# warship_demo_4.net
KiCad netlist of a schematic drawn in Altium Designer
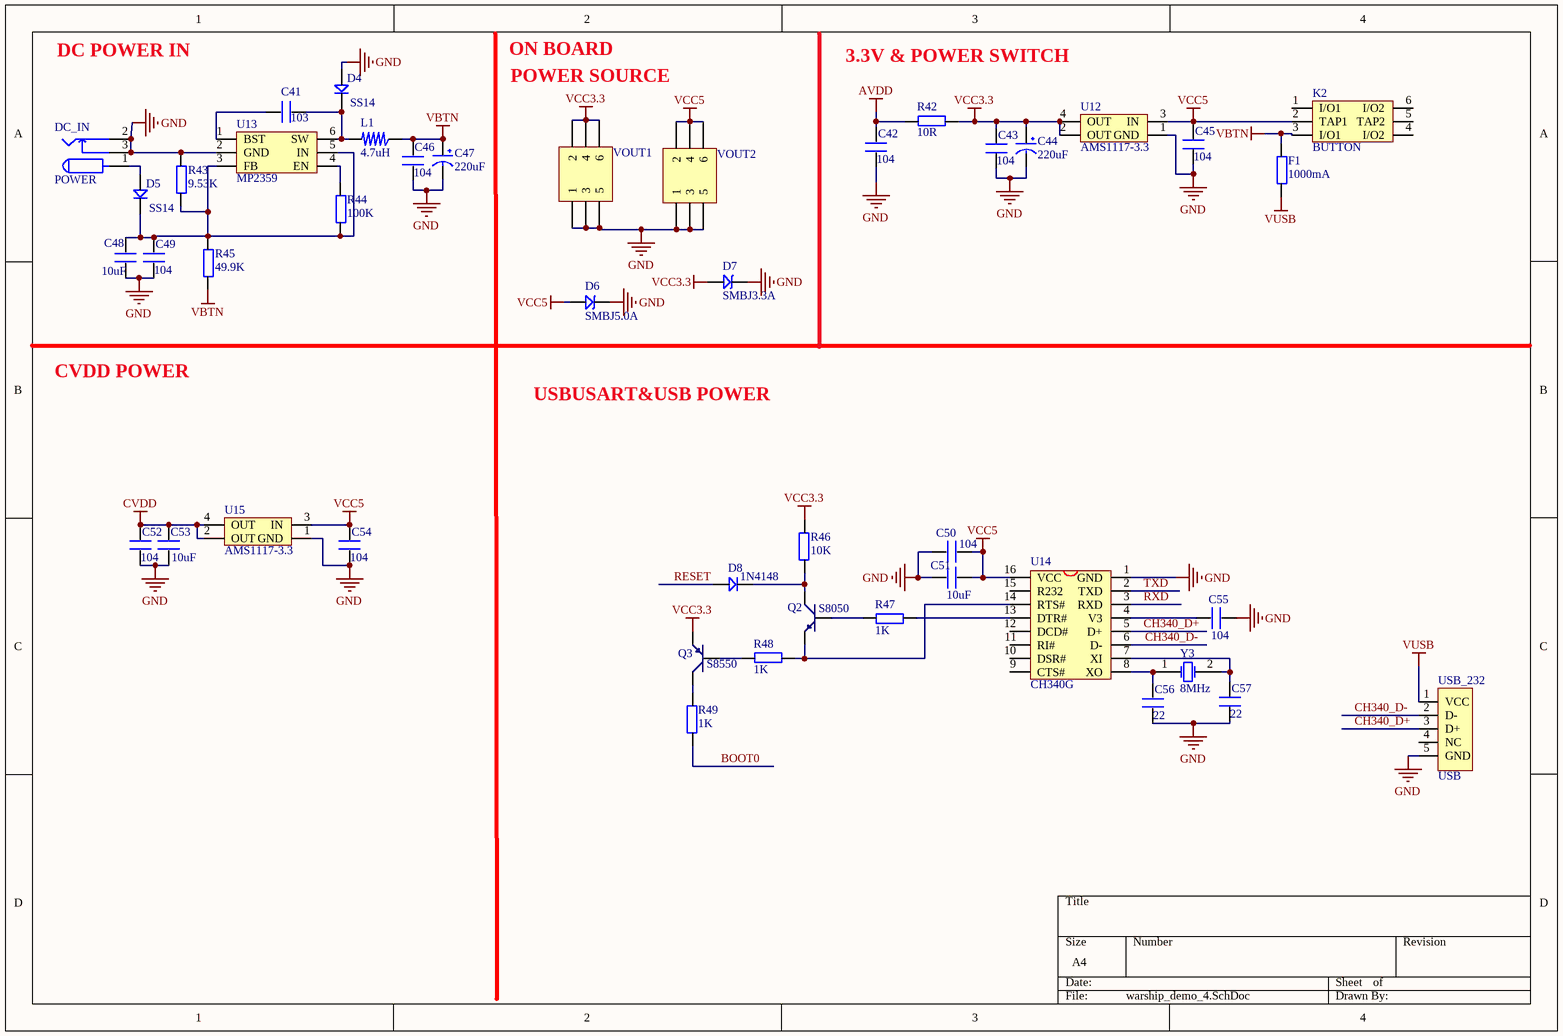
[diagram p0: warship_demo_4.SchDoc]

(export (version "E")
  (design (tool "Eeschema 10.0.6"))
  (components
    (comp (ref "C41") (value "103") (footprint "0603P") (libsource (lib "WarShip V3 STM32103封装库") (part "C")))
    (comp (ref "C42") (value "104") (footprint "0603P") (libsource (lib "WarShip V3 STM32103封装库") (part "C")))
    (comp (ref "C43") (value "104") (footprint "0603P") (libsource (lib "WarShip V3 STM32103封装库") (part "C")))
    (comp (ref "C44")
      (value "220uF")
      (footprint "CC6.56.5")
      (libsource (lib "WarShip V3 STM32103封装库") (part "CAP"))
    )
    (comp (ref "C45") (value "104") (footprint "0603P") (libsource (lib "WarShip V3 STM32103封装库") (part "C")))
    (comp (ref "C46") (value "104") (footprint "0603P") (libsource (lib "WarShip V3 STM32103封装库") (part "C")))
    (comp (ref "C47")
      (value "220uF")
      (footprint "CC6.56.5")
      (libsource (lib "WarShip V3 STM32103封装库") (part "CAP"))
    )
    (comp (ref "C48") (value "10uF") (footprint "1206") (libsource (lib "WarShip V3 STM32103封装库") (part "C")))
    (comp (ref "C49") (value "104") (footprint "0603P") (libsource (lib "WarShip V3 STM32103封装库") (part "C")))
    (comp (ref "C50") (value "104") (footprint "0603P") (libsource (lib "WarShip V3 STM32103封装库") (part "C")))
    (comp (ref "C51") (value "10uF") (footprint "0805") (libsource (lib "WarShip V3 STM32103封装库") (part "C")))
    (comp (ref "C52") (value "104") (footprint "0603P") (libsource (lib "WarShip V3 STM32103封装库") (part "C")))
    (comp (ref "C53") (value "10uF") (footprint "0805") (libsource (lib "WarShip V3 STM32103封装库") (part "C")))
    (comp (ref "C54") (value "104") (footprint "0603P") (libsource (lib "WarShip V3 STM32103封装库") (part "C")))
    (comp (ref "C55") (value "104") (footprint "0603P") (libsource (lib "WarShip V3 STM32103封装库") (part "C")))
    (comp (ref "C56") (value "22") (footprint "0603P") (libsource (lib "WarShip V3 STM32103封装库") (part "C")))
    (comp (ref "C57") (value "22") (footprint "0603P") (libsource (lib "WarShip V3 STM32103封装库") (part "C")))
    (comp (ref "D4")
      (value "SS14")
      (footprint "DIODE_3*5.3")
      (libsource (lib "WarShip V3 STM32103封装库") (part "D"))
    )
    (comp (ref "D5")
      (value "SS14")
      (footprint "DIODE_3*5.3")
      (libsource (lib "WarShip V3 STM32103封装库") (part "D"))
    )
    (comp (ref "D6")
      (value "SMBJ5.0A")
      (footprint "SMBJ")
      (description "TVS")
      (libsource (lib "WarShip V3 STM32103封装库") (part "SMBJ"))
    )
    (comp (ref "D7")
      (value "SMBJ3.3A")
      (footprint "SMBJ")
      (description "TVS")
      (libsource (lib "WarShip V3 STM32103封装库") (part "SMBJ"))
    )
    (comp (ref "D8")
      (value "1N4148")
      (footprint "DIODE_SOP")
      (libsource (lib "WarShip V3 STM32103封装库") (part "D"))
    )
    (comp (ref "DC_IN")
      (value "POWER")
      (footprint "DC10B")
      (libsource (lib "WarShip V3 STM32103封装库") (part "POW"))
    )
    (comp (ref "F1")
      (value "1000mA")
      (footprint "0805")
      (libsource (lib "WarShip V3 STM32103封装库") (part "R"))
    )
    (comp (ref "K2")
      (value "BUTTON")
      (footprint "BTN8.5*8.5")
      (libsource (lib "WarShip V3 STM32103封装库") (part "BUTTON"))
    )
    (comp (ref "L1")
      (value "4.7uH")
      (footprint "L_SOP74")
      (libsource (lib "WarShip V3 STM32103封装库") (part "L_SOP"))
    )
    (comp (ref "Q2")
      (value "S8050")
      (footprint "SOT-23R")
      (description "8050/BCW846/BCW847")
      (libsource (lib "WarShip V3 STM32103封装库") (part "NPN"))
    )
    (comp (ref "Q3")
      (value "S8550")
      (footprint "SOT-23R")
      (description "8550/BCW68")
      (libsource (lib "WarShip V3 STM32103封装库") (part "PNP"))
    )
    (comp (ref "R42") (value "10R") (footprint "0603P") (libsource (lib "WarShip V3 STM32103封装库") (part "R")))
    (comp (ref "R43")
      (value "9.53K")
      (footprint "0603P")
      (libsource (lib "WarShip V3 STM32103封装库") (part "R"))
    )
    (comp (ref "R44")
      (value "100K")
      (footprint "0603P")
      (libsource (lib "WarShip V3 STM32103封装库") (part "R"))
    )
    (comp (ref "R45")
      (value "49.9K")
      (footprint "0603P")
      (libsource (lib "WarShip V3 STM32103封装库") (part "R"))
    )
    (comp (ref "R46") (value "10K") (footprint "0603P") (libsource (lib "WarShip V3 STM32103封装库") (part "R")))
    (comp (ref "R47") (value "1K") (footprint "0603P") (libsource (lib "WarShip V3 STM32103封装库") (part "R")))
    (comp (ref "R48") (value "1K") (footprint "0603P") (libsource (lib "WarShip V3 STM32103封装库") (part "R")))
    (comp (ref "R49") (value "1K") (footprint "0603P") (libsource (lib "WarShip V3 STM32103封装库") (part "R")))
    (comp (ref "U12")
      (value "AMS1117-3.3")
      (footprint "AMS1117")
      (libsource (lib "WarShip V3 STM32103封装库") (part "AMS1117"))
    )
    (comp (ref "U13")
      (value "MP2359")
      (footprint "SOT-23-6")
      (description "DC DC Step Down IC")
      (libsource (lib "WarShip V3 STM32103封装库") (part "MP2359"))
    )
    (comp (ref "U14")
      (value "CH340G")
      (footprint "SOP16M")
      (description "USB2UART")
      (libsource (lib "WarShip V3 STM32103封装库") (part "CH340G"))
    )
    (comp (ref "U15")
      (value "AMS1117-3.3")
      (footprint "AMS1117")
      (libsource (lib "WarShip V3 STM32103封装库") (part "AMS1117"))
    )
    (comp (ref "USB_232")
      (value "USB")
      (footprint "USB/SM0.8-6H5")
      (libsource (lib "WarShip V3 STM32103封装库") (part "USB5"))
    )
    (comp (ref "VOUT1")
      (value "Header 3X2")
      (footprint "HDR2X3")
      (description "Header, 3-Pin, Dual row")
      (fields (field (name "PUBLISHER") "Altium Limited"))
      (libsource (lib "WarShip V3 STM32103封装库") (part "Header 3X2"))
    )
    (comp (ref "VOUT2")
      (value "Header 3X2")
      (footprint "HDR2X3")
      (description "Header, 3-Pin, Dual row")
      (fields (field (name "PUBLISHER") "Altium Limited"))
      (libsource (lib "WarShip V3 STM32103封装库") (part "Header 3X2"))
    )
    (comp (ref "Y3")
      (value "8MHz")
      (footprint "XTAL_US")
      (description "Crystal Oscillator")
      (fields (field (name "PUBLISHER") "Altium Limited"))
      (libsource (lib "WarShip V3 STM32103封装库") (part "XTAL"))
    )
  )
  (nets
    (net (code "1") (name "/BOOT0") (class "Default") (node (ref "R49") (pin "2") (pintype "passive")))
    (net (code "2") (name "/CH340_D+") (class "Default")
      (node (ref "U14") (pin "5") (pinfunction "D+_5") (pintype "passive"))
      (node (ref "USB_232") (pin "3") (pinfunction "D+_3") (pintype "passive"))
    )
    (net (code "3") (name "/CH340_D-") (class "Default")
      (node (ref "U14") (pin "6") (pinfunction "D-_6") (pintype "passive"))
      (node (ref "USB_232") (pin "2") (pinfunction "D-_2") (pintype "passive"))
    )
    (net (code "4") (name "/RESET") (class "Default") (node (ref "D8") (pin "1") (pintype "passive")))
    (net (code "5") (name "/RXD") (class "Default")
      (node (ref "U14") (pin "3") (pinfunction "RXD_3") (pintype "passive"))
    )
    (net (code "6") (name "/TXD") (class "Default")
      (node (ref "U14") (pin "2") (pinfunction "TXD_2") (pintype "passive"))
    )
    (net (code "7") (name "AVDD") (class "Default")
      (node (ref "C42") (pin "2") (pintype "passive"))
      (node (ref "R42") (pin "2") (pintype "passive"))
    )
    (net (code "8") (name "CVDD") (class "Default")
      (node (ref "C52") (pin "2") (pintype "passive"))
      (node (ref "C53") (pin "2") (pintype "passive"))
      (node (ref "U15") (pin "2") (pinfunction "OUT_2") (pintype "passive"))
      (node (ref "U15") (pin "4") (pinfunction "OUT_4") (pintype "passive"))
    )
    (net (code "9") (name "GND") (class "Default")
      (node (ref "C42") (pin "1") (pintype "passive"))
      (node (ref "C43") (pin "1") (pintype "passive"))
      (node (ref "C44") (pin "2") (pinfunction "GND_2") (pintype "passive"))
      (node (ref "C45") (pin "1") (pintype "passive"))
      (node (ref "C46") (pin "1") (pintype "passive"))
      (node (ref "C47") (pin "2") (pinfunction "GND_2") (pintype "passive"))
      (node (ref "C48") (pin "1") (pintype "passive"))
      (node (ref "C49") (pin "1") (pintype "passive"))
      (node (ref "C50") (pin "2") (pintype "passive"))
      (node (ref "C51") (pin "1") (pintype "passive"))
      (node (ref "C52") (pin "1") (pintype "passive"))
      (node (ref "C53") (pin "1") (pintype "passive"))
      (node (ref "C54") (pin "1") (pintype "passive"))
      (node (ref "C55") (pin "1") (pintype "passive"))
      (node (ref "C56") (pin "1") (pintype "passive"))
      (node (ref "C57") (pin "1") (pintype "passive"))
      (node (ref "D4") (pin "1") (pintype "passive"))
      (node (ref "D6") (pin "2") (pintype "passive"))
      (node (ref "D7") (pin "2") (pintype "passive"))
      (node (ref "DC_IN") (pin "2") (pintype "passive"))
      (node (ref "DC_IN") (pin "3") (pintype "passive"))
      (node (ref "R43") (pin "2") (pintype "passive"))
      (node (ref "U12") (pin "1") (pinfunction "GND_1") (pintype "passive"))
      (node (ref "U13") (pin "2") (pinfunction "GND_2") (pintype "passive"))
      (node (ref "U14") (pin "1") (pinfunction "GND_1") (pintype "passive"))
      (node (ref "U15") (pin "1") (pinfunction "GND_1") (pintype "passive"))
      (node (ref "USB_232") (pin "5") (pinfunction "GND_5") (pintype "passive"))
      (node (ref "VOUT1") (pin "1") (pinfunction "1_1") (pintype "passive"))
      (node (ref "VOUT1") (pin "3") (pinfunction "3_3") (pintype "passive"))
      (node (ref "VOUT1") (pin "5") (pinfunction "5_5") (pintype "passive"))
      (node (ref "VOUT2") (pin "1") (pinfunction "1_1") (pintype "passive"))
      (node (ref "VOUT2") (pin "3") (pinfunction "3_3") (pintype "passive"))
      (node (ref "VOUT2") (pin "5") (pinfunction "5_5") (pintype "passive"))
    )
    (net (code "10") (name "Net-(D5-Pad1)") (class "Default")
      (node (ref "D5") (pin "1") (pintype "passive"))
      (node (ref "DC_IN") (pin "1") (pintype "passive"))
    )
    (net (code "11") (name "Net-(Q2-B)") (class "Default")
      (node (ref "Q2") (pin "2") (pinfunction "B_2") (pintype "passive"))
      (node (ref "R47") (pin "1") (pintype "passive"))
    )
    (net (code "12") (name "Net-(Q2-C)") (class "Default")
      (node (ref "D8") (pin "2") (pintype "passive"))
      (node (ref "Q2") (pin "3") (pinfunction "C_3") (pintype "passive"))
      (node (ref "R46") (pin "2") (pintype "passive"))
    )
    (net (code "13") (name "Net-(Q2-E)") (class "Default")
      (node (ref "Q2") (pin "1") (pinfunction "E_1") (pintype "passive"))
      (node (ref "R48") (pin "1") (pintype "passive"))
      (node (ref "U14") (pin "14") (pinfunction "RTS#_14") (pintype "passive"))
    )
    (net (code "14") (name "Net-(Q3-B)") (class "Default")
      (node (ref "Q3") (pin "2") (pinfunction "B_2") (pintype "passive"))
      (node (ref "R48") (pin "2") (pintype "passive"))
    )
    (net (code "15") (name "Net-(Q3-C)") (class "Default")
      (node (ref "Q3") (pin "3") (pinfunction "C_3") (pintype "passive"))
      (node (ref "R49") (pin "1") (pintype "passive"))
    )
    (net (code "16") (name "Net-(U13-BST)") (class "Default")
      (node (ref "C41") (pin "2") (pintype "passive"))
      (node (ref "U13") (pin "1") (pinfunction "BST_1") (pintype "passive"))
    )
    (net (code "17") (name "Net-(U13-EN)") (class "Default")
      (node (ref "R44") (pin "2") (pintype "passive"))
      (node (ref "U13") (pin "4") (pinfunction "EN_4") (pintype "passive"))
    )
    (net (code "18") (name "Net-(U13-FB)") (class "Default")
      (node (ref "C48") (pin "2") (pintype "passive"))
      (node (ref "C49") (pin "2") (pintype "passive"))
      (node (ref "D5") (pin "2") (pintype "passive"))
      (node (ref "R43") (pin "1") (pintype "passive"))
      (node (ref "R44") (pin "1") (pintype "passive"))
      (node (ref "R45") (pin "2") (pintype "passive"))
      (node (ref "U13") (pin "3") (pinfunction "FB_3") (pintype "passive"))
      (node (ref "U13") (pin "5") (pinfunction "IN_5") (pintype "passive"))
    )
    (net (code "19") (name "Net-(U13-SW)") (class "Default")
      (node (ref "C41") (pin "1") (pintype "passive"))
      (node (ref "D4") (pin "2") (pintype "passive"))
      (node (ref "L1") (pin "2") (pinfunction "2_2") (pintype "passive"))
      (node (ref "U13") (pin "6") (pinfunction "SW_6") (pintype "passive"))
    )
    (net (code "20") (name "Net-(U14-DTR#)") (class "Default")
      (node (ref "R47") (pin "2") (pintype "passive"))
      (node (ref "U14") (pin "13") (pinfunction "DTR#_13") (pintype "passive"))
    )
    (net (code "21") (name "Net-(U14-V3)") (class "Default")
      (node (ref "C55") (pin "2") (pintype "passive"))
      (node (ref "U14") (pin "4") (pinfunction "V3_4") (pintype "passive"))
    )
    (net (code "22") (name "Net-(U14-XI)") (class "Default")
      (node (ref "C57") (pin "2") (pintype "passive"))
      (node (ref "U14") (pin "7") (pinfunction "XI_7") (pintype "passive"))
      (node (ref "Y3") (pin "2") (pinfunction "OSC2_2") (pintype "passive"))
    )
    (net (code "23") (name "Net-(U14-XO)") (class "Default")
      (node (ref "C56") (pin "2") (pintype "passive"))
      (node (ref "U14") (pin "8") (pinfunction "XO_8") (pintype "passive"))
      (node (ref "Y3") (pin "1") (pinfunction "OSC1_1") (pintype "passive"))
    )
    (net (code "24") (name "VBTN") (class "Default")
      (node (ref "C46") (pin "2") (pintype "passive"))
      (node (ref "C47") (pin "1") (pinfunction "VCC_1") (pintype "passive"))
      (node (ref "F1") (pin "2") (pintype "passive"))
      (node (ref "K2") (pin "3") (pinfunction "I/O1_3") (pintype "passive"))
      (node (ref "L1") (pin "1") (pinfunction "1_1") (pintype "passive"))
      (node (ref "R45") (pin "1") (pintype "passive"))
    )
    (net (code "25") (name "VCC3.3") (class "Default")
      (node (ref "C43") (pin "2") (pintype "passive"))
      (node (ref "C44") (pin "1") (pinfunction "VCC_1") (pintype "passive"))
      (node (ref "D7") (pin "1") (pintype "passive"))
      (node (ref "Q3") (pin "1") (pinfunction "E_1") (pintype "passive"))
      (node (ref "R42") (pin "1") (pintype "passive"))
      (node (ref "R46") (pin "1") (pintype "passive"))
      (node (ref "U12") (pin "2") (pinfunction "OUT_2") (pintype "passive"))
      (node (ref "U12") (pin "4") (pinfunction "OUT_4") (pintype "passive"))
      (node (ref "VOUT1") (pin "2") (pinfunction "2_2") (pintype "passive"))
      (node (ref "VOUT1") (pin "4") (pinfunction "4_4") (pintype "passive"))
      (node (ref "VOUT1") (pin "6") (pinfunction "6_6") (pintype "passive"))
    )
    (net (code "26") (name "VCC5") (class "Default")
      (node (ref "C45") (pin "2") (pintype "passive"))
      (node (ref "C50") (pin "1") (pintype "passive"))
      (node (ref "C51") (pin "2") (pintype "passive"))
      (node (ref "C54") (pin "2") (pintype "passive"))
      (node (ref "D6") (pin "1") (pintype "passive"))
      (node (ref "K2") (pin "2") (pinfunction "TAP1_2") (pintype "passive"))
      (node (ref "U12") (pin "3") (pinfunction "IN_3") (pintype "passive"))
      (node (ref "U14") (pin "16") (pinfunction "VCC_16") (pintype "passive"))
      (node (ref "U15") (pin "3") (pinfunction "IN_3") (pintype "passive"))
      (node (ref "VOUT2") (pin "2") (pinfunction "2_2") (pintype "passive"))
      (node (ref "VOUT2") (pin "4") (pinfunction "4_4") (pintype "passive"))
      (node (ref "VOUT2") (pin "6") (pinfunction "6_6") (pintype "passive"))
    )
    (net (code "27") (name "VUSB") (class "Default")
      (node (ref "F1") (pin "1") (pintype "passive"))
      (node (ref "USB_232") (pin "1") (pinfunction "VCC_1") (pintype "passive"))
    )
    (net (code "28") (name "unconnected-(K2-I{slash}O1-Pad1)") (class "Default")
      (node (ref "K2") (pin "1") (pinfunction "I/O1_1") (pintype "passive"))
    )
    (net (code "29") (name "unconnected-(K2-I{slash}O2-Pad4)") (class "Default")
      (node (ref "K2") (pin "4") (pinfunction "I/O2_4") (pintype "passive"))
    )
    (net (code "30") (name "unconnected-(K2-I{slash}O2-Pad6)") (class "Default")
      (node (ref "K2") (pin "6") (pinfunction "I/O2_6") (pintype "passive"))
    )
    (net (code "31") (name "unconnected-(K2-TAP2-Pad5)") (class "Default")
      (node (ref "K2") (pin "5") (pinfunction "TAP2_5") (pintype "passive"))
    )
    (net (code "32") (name "unconnected-(U14-CTS#-Pad9)") (class "Default")
      (node (ref "U14") (pin "9") (pinfunction "CTS#_9") (pintype "passive"))
    )
    (net (code "33") (name "unconnected-(U14-DCD#-Pad12)") (class "Default")
      (node (ref "U14") (pin "12") (pinfunction "DCD#_12") (pintype "passive"))
    )
    (net (code "34") (name "unconnected-(U14-DSR#-Pad10)") (class "Default")
      (node (ref "U14") (pin "10") (pinfunction "DSR#_10") (pintype "passive"))
    )
    (net (code "35") (name "unconnected-(U14-R232-Pad15)") (class "Default")
      (node (ref "U14") (pin "15") (pinfunction "R232_15") (pintype "passive"))
    )
    (net (code "36") (name "unconnected-(U14-RI#-Pad11)") (class "Default")
      (node (ref "U14") (pin "11") (pinfunction "RI#_11") (pintype "passive"))
    )
    (net (code "37") (name "unconnected-(USB_232-NC-Pad4)") (class "Default")
      (node (ref "USB_232") (pin "4") (pinfunction "NC_4") (pintype "passive"))
    )
  )
)
